# Peripherals.net
KiCad netlist of a schematic drawn in Altium Designer
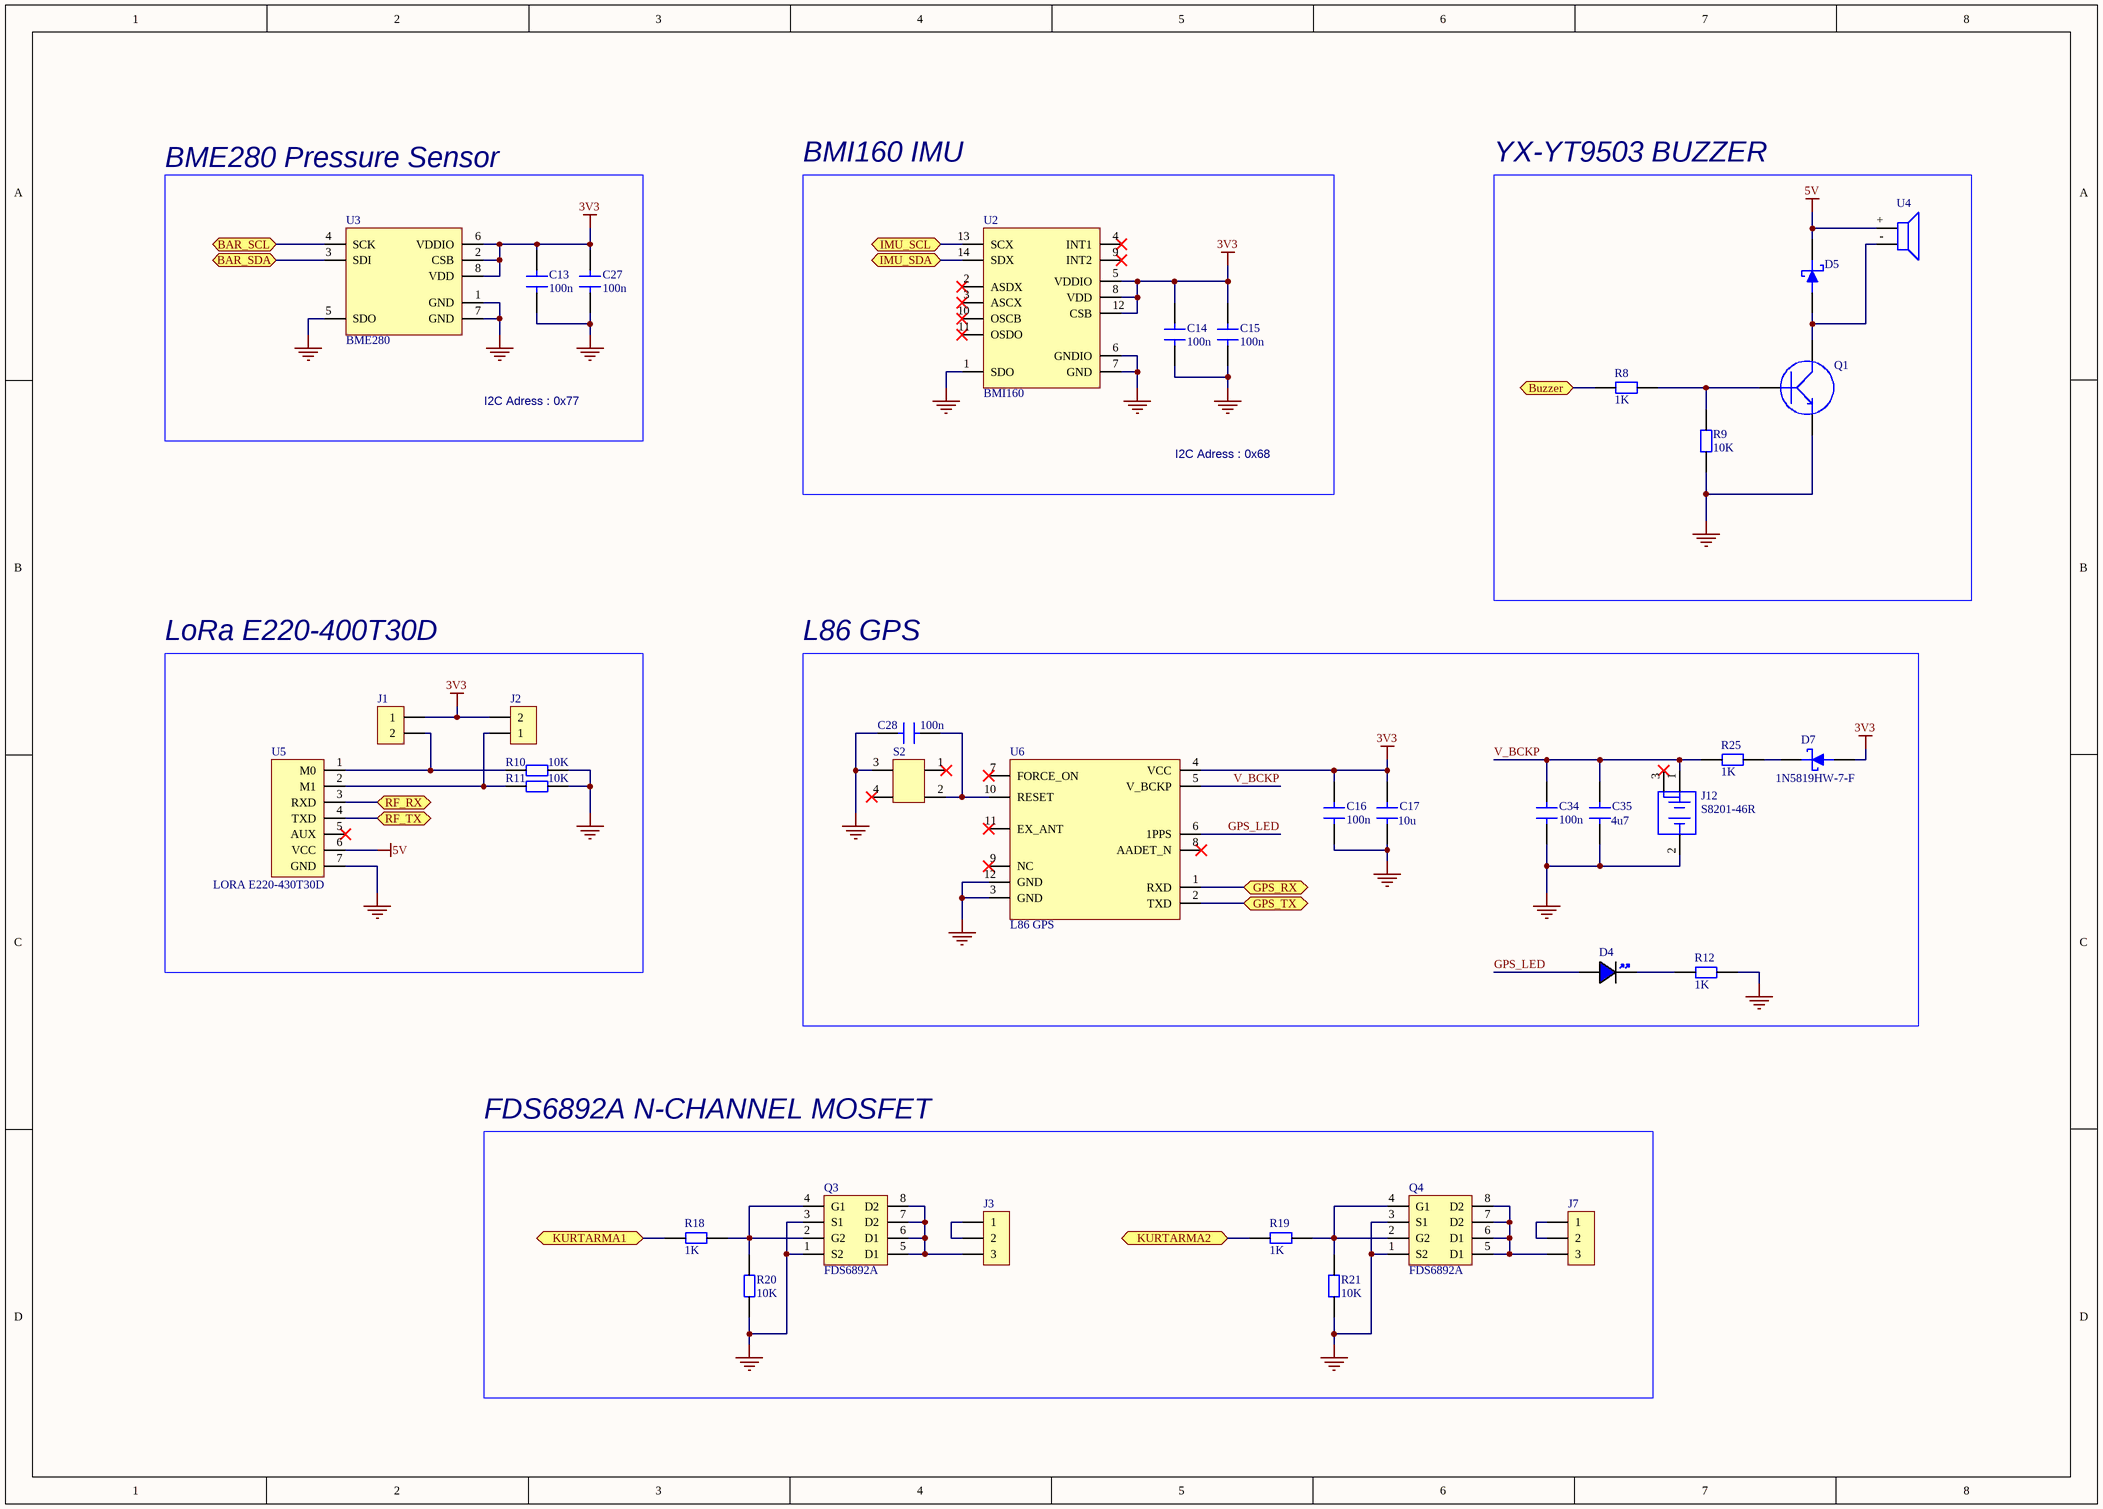
[diagram p0: Peripherals.SchDoc]

(export (version "E")
  (design (tool "Eeschema 10.0.6"))
  (components
    (comp (ref "C13")
      (value "100n")
      (footprint "CAP 0603")
      (description "Capacitor SMD 0603 50V")
      (libsource (lib "Schlib") (part "CAP 0603 50V"))
    )
    (comp (ref "C14")
      (value "100n")
      (footprint "CAP 0603")
      (description "Capacitor SMD 0603 50V")
      (libsource (lib "Schlib") (part "CAP 0603 50V"))
    )
    (comp (ref "C15")
      (value "100n")
      (footprint "CAP 0603")
      (description "Capacitor SMD 0603 50V")
      (libsource (lib "Schlib") (part "CAP 0603 50V"))
    )
    (comp (ref "C16")
      (value "100n")
      (footprint "CAP 0603")
      (description "Capacitor SMD 0603 50V")
      (libsource (lib "Schlib") (part "CAP 0603 50V"))
    )
    (comp (ref "C17")
      (value "10u")
      (footprint "CAP 0805")
      (description "Capacitor SMD 0805 25V")
      (libsource (lib "Schlib") (part "CAP 0805 25V"))
    )
    (comp (ref "C27")
      (value "100n")
      (footprint "CAP 0603")
      (description "Capacitor SMD 0603 50V")
      (libsource (lib "Schlib") (part "CAP 0603 50V"))
    )
    (comp (ref "C28")
      (value "100n")
      (footprint "CAP 0603")
      (description "Capacitor SMD 0603 50V")
      (libsource (lib "Schlib") (part "CAP 0603 50V"))
    )
    (comp (ref "C34")
      (value "100n")
      (footprint "CAP 0603")
      (description "Capacitor SMD 0603 50V")
      (libsource (lib "Schlib") (part "CAP 0603 50V"))
    )
    (comp (ref "C35")
      (value "4u7")
      (footprint "CAP 0805")
      (description "Capacitor SMD 0805 25V")
      (libsource (lib "Schlib") (part "CAP 0805 25V"))
    )
    (comp (ref "D4")
      (value "LED 0805 BLUE")
      (footprint "LED 0805 BLUE")
      (description "LED 0805 GREEN SMD")
      (libsource (lib "Schlib") (part "LED 0805 BLUE"))
    )
    (comp (ref "D5")
      (value "TMBAT49FILM")
      (footprint "TMBAT49FILM")
      (description "Rectifier Diode Small Signal Schottky Si 80V 0.5A 2-Pin MELF T/R")
      (fields (field (name "MANUFACTURER") "STMicroelectronics"))
      (libsource (lib "Schlib") (part "TMBAT49FILM"))
    )
    (comp (ref "D7")
      (value "1N5819HW-7-F")
      (footprint "1N5819HW-7-F")
      (description "Rectifier Diode, Schottky, 1 Phase, 1 Element, 1A, 40V V(RRM), Silicon")
      (fields (field (name "MANUFACTURER") "Diodes"))
      (libsource (lib "Schlib") (part "1N5819HW-7-F"))
    )
    (comp (ref "J1")
      (value "1x2 HEADER MALE")
      (footprint "1x2 HEADER MALE")
      (libsource (lib "Schlib") (part "1x2 HEADER MALE"))
    )
    (comp (ref "J2")
      (value "1x2 HEADER MALE")
      (footprint "1x2 HEADER MALE")
      (libsource (lib "") (part "1x2 HEADER MALE_1"))
    )
    (comp (ref "J3")
      (value "JST B3B-XH-A")
      (footprint "JST_B3B-XH-A")
      (description "Connector Header, XH Series, 3 Position, 2.50mm, Through Hole, Press-Fit, Solder, Natural")
      (fields
        (field (name "MANUFACTURER") "JST")
        (field (name "MANUFACTURER PART NUMBER") "B3B-XH-A(LF)(SN)")
      )
      (libsource (lib "Schlib") (part "JST B3B-XH-A"))
    )
    (comp (ref "J7")
      (value "JST B3B-XH-A")
      (footprint "JST_B3B-XH-A")
      (description "Connector Header, XH Series, 3 Position, 2.50mm, Through Hole, Press-Fit, Solder, Natural")
      (fields
        (field (name "MANUFACTURER") "JST")
        (field (name "MANUFACTURER PART NUMBER") "B3B-XH-A(LF)(SN)")
      )
      (libsource (lib "Schlib") (part "JST B3B-XH-A"))
    )
    (comp (ref "J12")
      (value "S8201-46R")
      (footprint "S8201-46R")
      (description "Battery Holder, Coin Cell, 1225, Smd Rohs Compliant: Yes ¦Harwin S8201-46R")
      (fields (field (name "MANUFACTURER") "Harwin"))
      (libsource (lib "Schlib") (part "S8201-46R"))
    )
    (comp (ref "Q1")
      (value "BC817-25W,115")
      (footprint "BC817-25")
      (description "BC817 Series 45 V 500 mA NPN General Purpose Transistor - SOT-23")
      (fields (field (name "MANUFACTURER") "Nexperia"))
      (libsource (lib "Schlib") (part "BC817-25W,115"))
    )
    (comp (ref "Q3")
      (value "FDS6892A")
      (footprint "DMG4822SSD-13")
      (description "Dual N-Channel Logic Level PWM Optimized PowerTrench® MOSFET 20V, 7.5A, 18mΩ")
      (fields (field (name "MANUFACTURER") "ON Semiconductor / Fairchild"))
      (libsource (lib "Schlib") (part "FDS6892A"))
    )
    (comp (ref "Q4")
      (value "FDS6892A")
      (footprint "DMG4822SSD-13")
      (description "Dual N-Channel Logic Level PWM Optimized PowerTrench® MOSFET 20V, 7.5A, 18mΩ")
      (fields (field (name "MANUFACTURER") "ON Semiconductor / Fairchild"))
      (libsource (lib "Schlib") (part "FDS6892A"))
    )
    (comp (ref "R8")
      (value "1K")
      (footprint "RES 0603")
      (description "Resistor SMD 0603")
      (libsource (lib "Schlib") (part "RES 0603"))
    )
    (comp (ref "R9")
      (value "10K")
      (footprint "RES 0603")
      (description "Resistor SMD 0603")
      (libsource (lib "Schlib") (part "RES 0603"))
    )
    (comp (ref "R10")
      (value "10K")
      (footprint "RES 0603")
      (description "Resistor SMD 0603")
      (libsource (lib "Schlib") (part "RES 0603"))
    )
    (comp (ref "R11")
      (value "10K")
      (footprint "RES 0603")
      (description "Resistor SMD 0603")
      (libsource (lib "Schlib") (part "RES 0603"))
    )
    (comp (ref "R12")
      (value "1K")
      (footprint "RES 0603")
      (description "Resistor SMD 0603")
      (libsource (lib "Schlib") (part "RES 0603"))
    )
    (comp (ref "R18")
      (value "1K")
      (footprint "RES 0805")
      (description "Resistor SMD 0805")
      (libsource (lib "Schlib") (part "RES 0805"))
    )
    (comp (ref "R19")
      (value "1K")
      (footprint "RES 0805")
      (description "Resistor SMD 0805")
      (libsource (lib "Schlib") (part "RES 0805"))
    )
    (comp (ref "R20")
      (value "10K")
      (footprint "RES 0805")
      (description "Resistor SMD 0805")
      (libsource (lib "Schlib") (part "RES 0805"))
    )
    (comp (ref "R21")
      (value "10K")
      (footprint "RES 0805")
      (description "Resistor SMD 0805")
      (libsource (lib "Schlib") (part "RES 0805"))
    )
    (comp (ref "R25")
      (value "1K")
      (footprint "RES 0603")
      (description "Resistor SMD 0603")
      (libsource (lib "Schlib") (part "RES 0603"))
    )
    (comp (ref "S2")
      (value "FSM4JSMATR")
      (footprint "FSM4JSMATR")
      (description "Switch Tactile OFF (ON) SPST Round Button Gull Wing 0.05A 24VDC 1.57N SMD T/R")
      (fields (field (name "MANUFACTURER") "TE Connectivity Alcoswitch"))
      (libsource (lib "Schlib") (part "FSM4JSMATR"))
    )
    (comp (ref "U2")
      (value "BMI160")
      (footprint "BMI160")
      (description "BMI160 2.5 x 3 mm Tiaxial Accelerometer / Gyroscope Inertial Measurement Unit")
      (fields (field (name "MANUFACTURER") "Bosch Tools"))
      (libsource (lib "Schlib") (part "BMI160"))
    )
    (comp (ref "U3")
      (value "BME280")
      (footprint "BME280")
      (description "SENSOR PRESSURE HUMIDITY TEMP")
      (fields (field (name "MANUFACTURER") "Bosch"))
      (libsource (lib "Schlib") (part "BME280"))
    )
    (comp (ref "U4")
      (value "YX-YT9503")
      (footprint "YX-YT9503")
      (description "BUZZER MAGNETIC WITH CIRCUIT 3V 2.7-KHZ THT")
      (libsource (lib "Schlib") (part "YX-YT9503"))
    )
    (comp (ref "U5")
      (value "LORA E220-430T30D")
      (footprint "LORA E220-400T30D")
      (description "E220-400T30D LoRa Module")
      (libsource (lib "Schlib") (part "LORA E220-430T30D"))
    )
    (comp (ref "U6") (value "L86 GPS") (footprint "L86") (libsource (lib "Schlib") (part "L86 GPS")))
  )
  (nets
    (net (code "1") (name "/BAR_SCL") (class "Default")
      (node (ref "U3") (pin "4") (pinfunction "SCK_4") (pintype "passive"))
    )
    (net (code "2") (name "/BAR_SDA") (class "Default")
      (node (ref "U3") (pin "3") (pinfunction "SDI_3") (pintype "passive"))
    )
    (net (code "3") (name "/Buzzer") (class "Default")
      (node (ref "R8") (pin "1") (pinfunction "1_1") (pintype "passive"))
    )
    (net (code "4") (name "/GPS_LED") (class "Default")
      (node (ref "D4") (pin "A") (pinfunction "A_A") (pintype "passive"))
      (node (ref "U6") (pin "6") (pinfunction "1PPS_6") (pintype "passive"))
    )
    (net (code "5") (name "/GPS_RX") (class "Default")
      (node (ref "U6") (pin "1") (pinfunction "RXD_1") (pintype "passive"))
    )
    (net (code "6") (name "/GPS_TX") (class "Default")
      (node (ref "U6") (pin "2") (pinfunction "TXD_2") (pintype "passive"))
    )
    (net (code "7") (name "/IMU_SCL") (class "Default")
      (node (ref "U2") (pin "13") (pinfunction "SCX_13") (pintype "passive"))
    )
    (net (code "8") (name "/IMU_SDA") (class "Default")
      (node (ref "U2") (pin "14") (pinfunction "SDX_14") (pintype "passive"))
    )
    (net (code "9") (name "/KURTARMA1") (class "Default")
      (node (ref "R18") (pin "1") (pinfunction "1_1") (pintype "passive"))
    )
    (net (code "10") (name "/KURTARMA2") (class "Default")
      (node (ref "R19") (pin "1") (pinfunction "1_1") (pintype "passive"))
    )
    (net (code "11") (name "/RF_RX") (class "Default")
      (node (ref "U5") (pin "3") (pinfunction "RXD_3") (pintype "passive"))
    )
    (net (code "12") (name "/RF_TX") (class "Default")
      (node (ref "U5") (pin "4") (pinfunction "TXD_4") (pintype "passive"))
    )
    (net (code "13") (name "/V_BCKP") (class "Default")
      (node (ref "C34") (pin "2") (pinfunction "2_2") (pintype "passive"))
      (node (ref "C35") (pin "2") (pinfunction "2_2") (pintype "passive"))
      (node (ref "J12") (pin "1") (pinfunction "+_1") (pintype "passive"))
      (node (ref "R25") (pin "1") (pinfunction "1_1") (pintype "passive"))
      (node (ref "U6") (pin "5") (pinfunction "V_BCKP_5") (pintype "passive"))
    )
    (net (code "14") (name "3V3") (class "Default")
      (node (ref "C13") (pin "2") (pinfunction "2_2") (pintype "passive"))
      (node (ref "C14") (pin "2") (pinfunction "2_2") (pintype "passive"))
      (node (ref "C15") (pin "2") (pinfunction "2_2") (pintype "passive"))
      (node (ref "C16") (pin "2") (pinfunction "2_2") (pintype "passive"))
      (node (ref "C17") (pin "2") (pinfunction "2_2") (pintype "passive"))
      (node (ref "C27") (pin "2") (pinfunction "2_2") (pintype "passive"))
      (node (ref "D7") (pin "C") (pintype "passive"))
      (node (ref "J1") (pin "1") (pinfunction "1_1") (pintype "passive"))
      (node (ref "J2") (pin "2") (pinfunction "2_2") (pintype "passive"))
      (node (ref "U2") (pin "12") (pinfunction "CSB_12") (pintype "passive"))
      (node (ref "U2") (pin "5") (pinfunction "VDDIO_5") (pintype "passive"))
      (node (ref "U2") (pin "8") (pinfunction "VDD_8") (pintype "passive"))
      (node (ref "U3") (pin "2") (pinfunction "CSB_2") (pintype "passive"))
      (node (ref "U3") (pin "6") (pinfunction "VDDIO_6") (pintype "passive"))
      (node (ref "U3") (pin "8") (pinfunction "VDD_8") (pintype "passive"))
      (node (ref "U6") (pin "4") (pinfunction "VCC_4") (pintype "passive"))
    )
    (net (code "15") (name "5V") (class "Default")
      (node (ref "D5") (pin "1") (pintype "passive"))
      (node (ref "U4") (pin "+") (pinfunction "+_+") (pintype "passive"))
      (node (ref "U5") (pin "6") (pinfunction "VCC_6") (pintype "passive"))
    )
    (net (code "16") (name "GND") (class "Default")
      (node (ref "C13") (pin "1") (pinfunction "1_1") (pintype "passive"))
      (node (ref "C14") (pin "1") (pinfunction "1_1") (pintype "passive"))
      (node (ref "C15") (pin "1") (pinfunction "1_1") (pintype "passive"))
      (node (ref "C16") (pin "1") (pinfunction "1_1") (pintype "passive"))
      (node (ref "C17") (pin "1") (pinfunction "1_1") (pintype "passive"))
      (node (ref "C27") (pin "1") (pinfunction "1_1") (pintype "passive"))
      (node (ref "C28") (pin "1") (pinfunction "1_1") (pintype "passive"))
      (node (ref "C34") (pin "1") (pinfunction "1_1") (pintype "passive"))
      (node (ref "C35") (pin "1") (pinfunction "1_1") (pintype "passive"))
      (node (ref "J12") (pin "2") (pinfunction "-_2") (pintype "passive"))
      (node (ref "Q1") (pin "2") (pinfunction "E_2") (pintype "passive"))
      (node (ref "Q3") (pin "1") (pinfunction "S2_1") (pintype "passive"))
      (node (ref "Q3") (pin "3") (pinfunction "S1_3") (pintype "passive"))
      (node (ref "Q4") (pin "1") (pinfunction "S2_1") (pintype "passive"))
      (node (ref "Q4") (pin "3") (pinfunction "S1_3") (pintype "passive"))
      (node (ref "R10") (pin "2") (pinfunction "2_2") (pintype "passive"))
      (node (ref "R11") (pin "2") (pinfunction "2_2") (pintype "passive"))
      (node (ref "R12") (pin "2") (pinfunction "2_2") (pintype "passive"))
      (node (ref "R20") (pin "1") (pinfunction "1_1") (pintype "passive"))
      (node (ref "R21") (pin "1") (pinfunction "1_1") (pintype "passive"))
      (node (ref "R9") (pin "1") (pinfunction "1_1") (pintype "passive"))
      (node (ref "S2") (pin "3") (pinfunction "3_3") (pintype "passive"))
      (node (ref "U2") (pin "1") (pinfunction "SDO_1") (pintype "passive"))
      (node (ref "U2") (pin "6") (pinfunction "GNDIO_6") (pintype "passive"))
      (node (ref "U2") (pin "7") (pinfunction "GND_7") (pintype "passive"))
      (node (ref "U3") (pin "1") (pinfunction "GND_1") (pintype "passive"))
      (node (ref "U3") (pin "5") (pinfunction "SDO_5") (pintype "passive"))
      (node (ref "U3") (pin "7") (pinfunction "GND_7") (pintype "passive"))
      (node (ref "U5") (pin "7") (pinfunction "GND_7") (pintype "passive"))
      (node (ref "U6") (pin "12") (pinfunction "GND_12") (pintype "passive"))
      (node (ref "U6") (pin "3") (pinfunction "GND_3") (pintype "passive"))
    )
    (net (code "17") (name "Net-(D4-PadK)") (class "Default")
      (node (ref "D4") (pin "K") (pinfunction "K_K") (pintype "passive"))
      (node (ref "R12") (pin "1") (pinfunction "1_1") (pintype "passive"))
    )
    (net (code "18") (name "Net-(D7-PadA)") (class "Default")
      (node (ref "D7") (pin "A") (pintype "passive"))
      (node (ref "R25") (pin "2") (pinfunction "2_2") (pintype "passive"))
    )
    (net (code "19") (name "Net-(J3-Pad1)") (class "Default")
      (node (ref "J3") (pin "1") (pinfunction "1_1") (pintype "passive"))
      (node (ref "J3") (pin "2") (pinfunction "2_2") (pintype "passive"))
    )
    (net (code "20") (name "Net-(J3-Pad3)") (class "Default")
      (node (ref "J3") (pin "3") (pinfunction "3_3") (pintype "passive"))
      (node (ref "Q3") (pin "5") (pinfunction "D1_5") (pintype "passive"))
      (node (ref "Q3") (pin "6") (pinfunction "D1_6") (pintype "passive"))
      (node (ref "Q3") (pin "7") (pinfunction "D2_7") (pintype "passive"))
      (node (ref "Q3") (pin "8") (pinfunction "D2_8") (pintype "passive"))
    )
    (net (code "21") (name "Net-(J7-Pad1)") (class "Default")
      (node (ref "J7") (pin "1") (pinfunction "1_1") (pintype "passive"))
      (node (ref "J7") (pin "2") (pinfunction "2_2") (pintype "passive"))
    )
    (net (code "22") (name "Net-(J7-Pad3)") (class "Default")
      (node (ref "J7") (pin "3") (pinfunction "3_3") (pintype "passive"))
      (node (ref "Q4") (pin "5") (pinfunction "D1_5") (pintype "passive"))
      (node (ref "Q4") (pin "6") (pinfunction "D1_6") (pintype "passive"))
      (node (ref "Q4") (pin "7") (pinfunction "D2_7") (pintype "passive"))
      (node (ref "Q4") (pin "8") (pinfunction "D2_8") (pintype "passive"))
    )
    (net (code "23") (name "Net-(Q1-B)") (class "Default")
      (node (ref "Q1") (pin "1") (pinfunction "B_1") (pintype "passive"))
      (node (ref "R8") (pin "2") (pinfunction "2_2") (pintype "passive"))
      (node (ref "R9") (pin "2") (pinfunction "2_2") (pintype "passive"))
    )
    (net (code "24") (name "Net-(Q1-C)") (class "Default")
      (node (ref "D5") (pin "2") (pintype "passive"))
      (node (ref "Q1") (pin "3") (pinfunction "C_3") (pintype "passive"))
      (node (ref "U4") (pin "-") (pinfunction "-_-") (pintype "passive"))
    )
    (net (code "25") (name "Net-(Q3-G1)") (class "Default")
      (node (ref "Q3") (pin "2") (pinfunction "G2_2") (pintype "passive"))
      (node (ref "Q3") (pin "4") (pinfunction "G1_4") (pintype "passive"))
      (node (ref "R18") (pin "2") (pinfunction "2_2") (pintype "passive"))
      (node (ref "R20") (pin "2") (pinfunction "2_2") (pintype "passive"))
    )
    (net (code "26") (name "Net-(Q4-G1)") (class "Default")
      (node (ref "Q4") (pin "2") (pinfunction "G2_2") (pintype "passive"))
      (node (ref "Q4") (pin "4") (pinfunction "G1_4") (pintype "passive"))
      (node (ref "R19") (pin "2") (pinfunction "2_2") (pintype "passive"))
      (node (ref "R21") (pin "2") (pinfunction "2_2") (pintype "passive"))
    )
    (net (code "27") (name "Net-(U5-M0)") (class "Default")
      (node (ref "J1") (pin "2") (pinfunction "2_2") (pintype "passive"))
      (node (ref "R10") (pin "1") (pinfunction "1_1") (pintype "passive"))
      (node (ref "U5") (pin "1") (pinfunction "M0_1") (pintype "passive"))
    )
    (net (code "28") (name "Net-(U5-M1)") (class "Default")
      (node (ref "J2") (pin "1") (pinfunction "1_1") (pintype "passive"))
      (node (ref "R11") (pin "1") (pinfunction "1_1") (pintype "passive"))
      (node (ref "U5") (pin "2") (pinfunction "M1_2") (pintype "passive"))
    )
    (net (code "29") (name "Net-(U6-RESET)") (class "Default")
      (node (ref "C28") (pin "2") (pinfunction "2_2") (pintype "passive"))
      (node (ref "S2") (pin "2") (pinfunction "2_2") (pintype "passive"))
      (node (ref "U6") (pin "10") (pinfunction "RESET_10") (pintype "passive"))
    )
    (net (code "30") (name "unconnected-(J12-+-Pad3)") (class "Default")
      (node (ref "J12") (pin "3") (pinfunction "+_3") (pintype "passive+no_connect"))
    )
    (net (code "31") (name "unconnected-(S2-Pad1)") (class "Default")
      (node (ref "S2") (pin "1") (pinfunction "1_1") (pintype "passive+no_connect"))
    )
    (net (code "32") (name "unconnected-(S2-Pad4)") (class "Default")
      (node (ref "S2") (pin "4") (pinfunction "4_4") (pintype "passive+no_connect"))
    )
    (net (code "33") (name "unconnected-(U2-ASCX-Pad3)") (class "Default")
      (node (ref "U2") (pin "3") (pinfunction "ASCX_3") (pintype "passive+no_connect"))
    )
    (net (code "34") (name "unconnected-(U2-ASDX-Pad2)") (class "Default")
      (node (ref "U2") (pin "2") (pinfunction "ASDX_2") (pintype "passive+no_connect"))
    )
    (net (code "35") (name "unconnected-(U2-INT1-Pad4)") (class "Default")
      (node (ref "U2") (pin "4") (pinfunction "INT1_4") (pintype "passive+no_connect"))
    )
    (net (code "36") (name "unconnected-(U2-INT2-Pad9)") (class "Default")
      (node (ref "U2") (pin "9") (pinfunction "INT2_9") (pintype "passive+no_connect"))
    )
    (net (code "37") (name "unconnected-(U2-OSCB-Pad10)") (class "Default")
      (node (ref "U2") (pin "10") (pinfunction "OSCB_10") (pintype "passive+no_connect"))
    )
    (net (code "38") (name "unconnected-(U2-OSDO-Pad11)") (class "Default")
      (node (ref "U2") (pin "11") (pinfunction "OSDO_11") (pintype "passive+no_connect"))
    )
    (net (code "39") (name "unconnected-(U5-AUX-Pad5)") (class "Default")
      (node (ref "U5") (pin "5") (pinfunction "AUX_5") (pintype "passive+no_connect"))
    )
    (net (code "40") (name "unconnected-(U6-AADET_N-Pad8)") (class "Default")
      (node (ref "U6") (pin "8") (pinfunction "AADET_N_8") (pintype "passive+no_connect"))
    )
    (net (code "41") (name "unconnected-(U6-EX_ANT-Pad11)") (class "Default")
      (node (ref "U6") (pin "11") (pinfunction "EX_ANT_11") (pintype "passive+no_connect"))
    )
    (net (code "42") (name "unconnected-(U6-FORCE_ON-Pad7)") (class "Default")
      (node (ref "U6") (pin "7") (pinfunction "FORCE_ON_7") (pintype "passive+no_connect"))
    )
    (net (code "43") (name "unconnected-(U6-NC-Pad9)") (class "Default")
      (node (ref "U6") (pin "9") (pinfunction "NC_9") (pintype "passive+no_connect"))
    )
  )
)
